# board.net
KiCad netlist of a schematic drawn in EAGLE
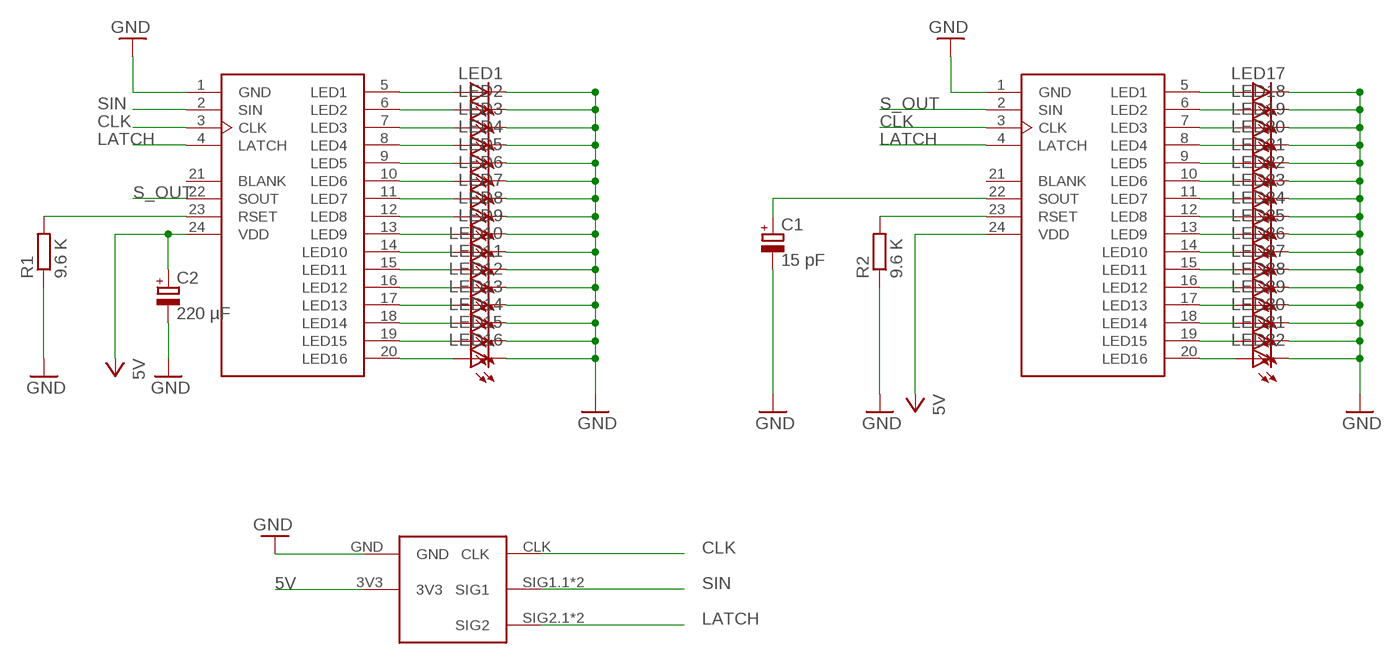
[diagram p0: schematic, sheet 1]

(export (version "E")
  (design (tool "Eeschema 10.0.6"))
  (components
    (comp (ref "C1")
      (value "15 pF")
      (footprint "eagle-import:E5-8,5")
      (libsource (lib "eagle-import") (part "CPOL-EUE5-8.5"))
    )
    (comp (ref "C2")
      (value "220 µF")
      (footprint "eagle-import:E5-8,5")
      (libsource (lib "eagle-import") (part "CPOL-EUE5-8.5"))
    )
    (comp (ref "IC1")
      (value "CAT4016")
      (footprint "eagle-import:SOIC24W")
      (libsource (lib "eagle-import") (part "CAT4016"))
    )
    (comp (ref "IC2")
      (value "CAT4016")
      (footprint "eagle-import:SOIC24W")
      (libsource (lib "eagle-import") (part "CAT4016"))
    )
    (comp (ref "LED1")
      (value "LEDCHIPLED-0603-TTW")
      (footprint "eagle-import:CHIPLED-0603-TTW")
      (libsource (lib "eagle-import") (part "LEDCHIPLED-0603-TTW"))
    )
    (comp (ref "LED2")
      (value "LEDCHIPLED-0603-TTW")
      (footprint "eagle-import:CHIPLED-0603-TTW")
      (libsource (lib "eagle-import") (part "LEDCHIPLED-0603-TTW"))
    )
    (comp (ref "LED3")
      (value "LEDCHIPLED-0603-TTW")
      (footprint "eagle-import:CHIPLED-0603-TTW")
      (libsource (lib "eagle-import") (part "LEDCHIPLED-0603-TTW"))
    )
    (comp (ref "LED4")
      (value "LEDCHIPLED-0603-TTW")
      (footprint "eagle-import:CHIPLED-0603-TTW")
      (libsource (lib "eagle-import") (part "LEDCHIPLED-0603-TTW"))
    )
    (comp (ref "LED5")
      (value "LEDCHIPLED-0603-TTW")
      (footprint "eagle-import:CHIPLED-0603-TTW")
      (libsource (lib "eagle-import") (part "LEDCHIPLED-0603-TTW"))
    )
    (comp (ref "LED6")
      (value "LEDCHIPLED-0603-TTW")
      (footprint "eagle-import:CHIPLED-0603-TTW")
      (libsource (lib "eagle-import") (part "LEDCHIPLED-0603-TTW"))
    )
    (comp (ref "LED7")
      (value "LEDCHIPLED-0603-TTW")
      (footprint "eagle-import:CHIPLED-0603-TTW")
      (libsource (lib "eagle-import") (part "LEDCHIPLED-0603-TTW"))
    )
    (comp (ref "LED8")
      (value "LEDCHIPLED-0603-TTW")
      (footprint "eagle-import:CHIPLED-0603-TTW")
      (libsource (lib "eagle-import") (part "LEDCHIPLED-0603-TTW"))
    )
    (comp (ref "LED9")
      (value "LEDCHIPLED-0603-TTW")
      (footprint "eagle-import:CHIPLED-0603-TTW")
      (libsource (lib "eagle-import") (part "LEDCHIPLED-0603-TTW"))
    )
    (comp (ref "LED10")
      (value "LEDCHIPLED-0603-TTW")
      (footprint "eagle-import:CHIPLED-0603-TTW")
      (libsource (lib "eagle-import") (part "LEDCHIPLED-0603-TTW"))
    )
    (comp (ref "LED11")
      (value "LEDCHIPLED-0603-TTW")
      (footprint "eagle-import:CHIPLED-0603-TTW")
      (libsource (lib "eagle-import") (part "LEDCHIPLED-0603-TTW"))
    )
    (comp (ref "LED12")
      (value "LEDCHIPLED-0603-TTW")
      (footprint "eagle-import:CHIPLED-0603-TTW")
      (libsource (lib "eagle-import") (part "LEDCHIPLED-0603-TTW"))
    )
    (comp (ref "LED13")
      (value "LEDCHIPLED-0603-TTW")
      (footprint "eagle-import:CHIPLED-0603-TTW")
      (libsource (lib "eagle-import") (part "LEDCHIPLED-0603-TTW"))
    )
    (comp (ref "LED14")
      (value "LEDCHIPLED-0603-TTW")
      (footprint "eagle-import:CHIPLED-0603-TTW")
      (libsource (lib "eagle-import") (part "LEDCHIPLED-0603-TTW"))
    )
    (comp (ref "LED15")
      (value "LEDCHIPLED-0603-TTW")
      (footprint "eagle-import:CHIPLED-0603-TTW")
      (libsource (lib "eagle-import") (part "LEDCHIPLED-0603-TTW"))
    )
    (comp (ref "LED16")
      (value "LEDCHIPLED-0603-TTW")
      (footprint "eagle-import:CHIPLED-0603-TTW")
      (libsource (lib "eagle-import") (part "LEDCHIPLED-0603-TTW"))
    )
    (comp (ref "LED17")
      (value "LEDCHIPLED-0603-TTW")
      (footprint "eagle-import:CHIPLED-0603-TTW")
      (libsource (lib "eagle-import") (part "LEDCHIPLED-0603-TTW"))
    )
    (comp (ref "LED18")
      (value "LEDCHIPLED-0603-TTW")
      (footprint "eagle-import:CHIPLED-0603-TTW")
      (libsource (lib "eagle-import") (part "LEDCHIPLED-0603-TTW"))
    )
    (comp (ref "LED19")
      (value "LEDCHIPLED-0603-TTW")
      (footprint "eagle-import:CHIPLED-0603-TTW")
      (libsource (lib "eagle-import") (part "LEDCHIPLED-0603-TTW"))
    )
    (comp (ref "LED20")
      (value "LEDCHIPLED-0603-TTW")
      (footprint "eagle-import:CHIPLED-0603-TTW")
      (libsource (lib "eagle-import") (part "LEDCHIPLED-0603-TTW"))
    )
    (comp (ref "LED21")
      (value "LEDCHIPLED-0603-TTW")
      (footprint "eagle-import:CHIPLED-0603-TTW")
      (libsource (lib "eagle-import") (part "LEDCHIPLED-0603-TTW"))
    )
    (comp (ref "LED22")
      (value "LEDCHIPLED-0603-TTW")
      (footprint "eagle-import:CHIPLED-0603-TTW")
      (libsource (lib "eagle-import") (part "LEDCHIPLED-0603-TTW"))
    )
    (comp (ref "LED23")
      (value "LEDCHIPLED-0603-TTW")
      (footprint "eagle-import:CHIPLED-0603-TTW")
      (libsource (lib "eagle-import") (part "LEDCHIPLED-0603-TTW"))
    )
    (comp (ref "LED24")
      (value "LEDCHIPLED-0603-TTW")
      (footprint "eagle-import:CHIPLED-0603-TTW")
      (libsource (lib "eagle-import") (part "LEDCHIPLED-0603-TTW"))
    )
    (comp (ref "LED25")
      (value "LEDCHIPLED-0603-TTW")
      (footprint "eagle-import:CHIPLED-0603-TTW")
      (libsource (lib "eagle-import") (part "LEDCHIPLED-0603-TTW"))
    )
    (comp (ref "LED26")
      (value "LEDCHIPLED-0603-TTW")
      (footprint "eagle-import:CHIPLED-0603-TTW")
      (libsource (lib "eagle-import") (part "LEDCHIPLED-0603-TTW"))
    )
    (comp (ref "LED27")
      (value "LEDCHIPLED-0603-TTW")
      (footprint "eagle-import:CHIPLED-0603-TTW")
      (libsource (lib "eagle-import") (part "LEDCHIPLED-0603-TTW"))
    )
    (comp (ref "LED28")
      (value "LEDCHIPLED-0603-TTW")
      (footprint "eagle-import:CHIPLED-0603-TTW")
      (libsource (lib "eagle-import") (part "LEDCHIPLED-0603-TTW"))
    )
    (comp (ref "LED29")
      (value "LEDCHIPLED-0603-TTW")
      (footprint "eagle-import:CHIPLED-0603-TTW")
      (libsource (lib "eagle-import") (part "LEDCHIPLED-0603-TTW"))
    )
    (comp (ref "LED30")
      (value "LEDCHIPLED-0603-TTW")
      (footprint "eagle-import:CHIPLED-0603-TTW")
      (libsource (lib "eagle-import") (part "LEDCHIPLED-0603-TTW"))
    )
    (comp (ref "LED31")
      (value "LEDCHIPLED-0603-TTW")
      (footprint "eagle-import:CHIPLED-0603-TTW")
      (libsource (lib "eagle-import") (part "LEDCHIPLED-0603-TTW"))
    )
    (comp (ref "LED32")
      (value "LEDCHIPLED-0603-TTW")
      (footprint "eagle-import:CHIPLED-0603-TTW")
      (libsource (lib "eagle-import") (part "LEDCHIPLED-0603-TTW"))
    )
    (comp (ref "R1")
      (value "9.6 K")
      (footprint "eagle-import:0207_10")
      (libsource (lib "eagle-import") (part "R-EU_0207/10"))
    )
    (comp (ref "R2")
      (value "9.6 K")
      (footprint "eagle-import:0207_10")
      (libsource (lib "eagle-import") (part "R-EU_0207/10"))
    )
    (comp (ref "U$1")
      (value "SLIP-RING-INVERSE")
      (footprint "eagle-import:SLIP-RING-INVERSE")
      (libsource (lib "eagle-import") (part "SLIP-RING-INVERSE"))
    )
  )
  (nets
    (net (code "1") (name "/CLK") (class "Default")
      (node (ref "IC1") (pin "3") (pinfunction "CLK_3") (pintype "bidirectional"))
      (node (ref "IC2") (pin "3") (pinfunction "CLK_3") (pintype "bidirectional"))
      (node (ref "U$1") (pin "CLK") (pinfunction "CLK_CLK") (pintype "bidirectional"))
    )
    (net (code "2") (name "/LATCH") (class "Default")
      (node (ref "IC1") (pin "4") (pinfunction "LATCH_4") (pintype "bidirectional"))
      (node (ref "IC2") (pin "4") (pinfunction "LATCH_4") (pintype "bidirectional"))
      (node (ref "U$1") (pin "SIG2.1") (pinfunction "SIG2_SIG2.1") (pintype "bidirectional"))
      (node (ref "U$1") (pin "SIG2.2") (pinfunction "SIG2_SIG2.2") (pintype "bidirectional"))
    )
    (net (code "3") (name "/SIN") (class "Default")
      (node (ref "IC1") (pin "2") (pinfunction "SIN_2") (pintype "bidirectional"))
      (node (ref "U$1") (pin "SIG1.1") (pinfunction "SIG1_SIG1.1") (pintype "bidirectional"))
      (node (ref "U$1") (pin "SIG1.2") (pinfunction "SIG1_SIG1.2") (pintype "bidirectional"))
    )
    (net (code "4") (name "/S_OUT") (class "Default")
      (node (ref "IC1") (pin "22") (pinfunction "SOUT_22") (pintype "bidirectional"))
      (node (ref "IC2") (pin "2") (pinfunction "SIN_2") (pintype "bidirectional"))
    )
    (net (code "5") (name "5V") (class "Default")
      (node (ref "C2") (pin "+") (pinfunction "+_+") (pintype "passive"))
      (node (ref "IC1") (pin "24") (pinfunction "VDD_24") (pintype "bidirectional"))
      (node (ref "IC2") (pin "24") (pinfunction "VDD_24") (pintype "bidirectional"))
      (node (ref "U$1") (pin "3V3") (pinfunction "3V3_3V3") (pintype "bidirectional"))
    )
    (net (code "6") (name "GND") (class "Default")
      (node (ref "C1") (pin "-") (pinfunction "-_-") (pintype "passive"))
      (node (ref "C2") (pin "-") (pinfunction "-_-") (pintype "passive"))
      (node (ref "IC1") (pin "1") (pinfunction "GND_1") (pintype "bidirectional"))
      (node (ref "IC2") (pin "1") (pinfunction "GND_1") (pintype "bidirectional"))
      (node (ref "LED1") (pin "C@1") (pinfunction "C_C@1") (pintype "passive"))
      (node (ref "LED10") (pin "C@1") (pinfunction "C_C@1") (pintype "passive"))
      (node (ref "LED11") (pin "C@1") (pinfunction "C_C@1") (pintype "passive"))
      (node (ref "LED12") (pin "C@1") (pinfunction "C_C@1") (pintype "passive"))
      (node (ref "LED13") (pin "C@1") (pinfunction "C_C@1") (pintype "passive"))
      (node (ref "LED14") (pin "C@1") (pinfunction "C_C@1") (pintype "passive"))
      (node (ref "LED15") (pin "C@1") (pinfunction "C_C@1") (pintype "passive"))
      (node (ref "LED16") (pin "C@1") (pinfunction "C_C@1") (pintype "passive"))
      (node (ref "LED17") (pin "C@1") (pinfunction "C_C@1") (pintype "passive"))
      (node (ref "LED18") (pin "C@1") (pinfunction "C_C@1") (pintype "passive"))
      (node (ref "LED19") (pin "C@1") (pinfunction "C_C@1") (pintype "passive"))
      (node (ref "LED2") (pin "C@1") (pinfunction "C_C@1") (pintype "passive"))
      (node (ref "LED20") (pin "C@1") (pinfunction "C_C@1") (pintype "passive"))
      (node (ref "LED21") (pin "C@1") (pinfunction "C_C@1") (pintype "passive"))
      (node (ref "LED22") (pin "C@1") (pinfunction "C_C@1") (pintype "passive"))
      (node (ref "LED23") (pin "C@1") (pinfunction "C_C@1") (pintype "passive"))
      (node (ref "LED24") (pin "C@1") (pinfunction "C_C@1") (pintype "passive"))
      (node (ref "LED25") (pin "C@1") (pinfunction "C_C@1") (pintype "passive"))
      (node (ref "LED26") (pin "C@1") (pinfunction "C_C@1") (pintype "passive"))
      (node (ref "LED27") (pin "C@1") (pinfunction "C_C@1") (pintype "passive"))
      (node (ref "LED28") (pin "C@1") (pinfunction "C_C@1") (pintype "passive"))
      (node (ref "LED29") (pin "C@1") (pinfunction "C_C@1") (pintype "passive"))
      (node (ref "LED3") (pin "C@1") (pinfunction "C_C@1") (pintype "passive"))
      (node (ref "LED30") (pin "C@1") (pinfunction "C_C@1") (pintype "passive"))
      (node (ref "LED31") (pin "C@1") (pinfunction "C_C@1") (pintype "passive"))
      (node (ref "LED32") (pin "C@1") (pinfunction "C_C@1") (pintype "passive"))
      (node (ref "LED4") (pin "C@1") (pinfunction "C_C@1") (pintype "passive"))
      (node (ref "LED5") (pin "C@1") (pinfunction "C_C@1") (pintype "passive"))
      (node (ref "LED6") (pin "C@1") (pinfunction "C_C@1") (pintype "passive"))
      (node (ref "LED7") (pin "C@1") (pinfunction "C_C@1") (pintype "passive"))
      (node (ref "LED8") (pin "C@1") (pinfunction "C_C@1") (pintype "passive"))
      (node (ref "LED9") (pin "C@1") (pinfunction "C_C@1") (pintype "passive"))
      (node (ref "R1") (pin "1") (pinfunction "1_1") (pintype "passive"))
      (node (ref "R2") (pin "1") (pinfunction "1_1") (pintype "passive"))
      (node (ref "U$1") (pin "GND") (pinfunction "GND_GND") (pintype "bidirectional"))
    )
    (net (code "7") (name "Net-(IC1-LED1)") (class "Default")
      (node (ref "IC1") (pin "5") (pinfunction "LED1_5") (pintype "bidirectional"))
      (node (ref "LED1") (pin "A@1") (pinfunction "A_A@1") (pintype "passive"))
    )
    (net (code "8") (name "Net-(IC1-LED2)") (class "Default")
      (node (ref "IC1") (pin "6") (pinfunction "LED2_6") (pintype "bidirectional"))
      (node (ref "LED2") (pin "A@1") (pinfunction "A_A@1") (pintype "passive"))
    )
    (net (code "9") (name "Net-(IC1-LED3)") (class "Default")
      (node (ref "IC1") (pin "7") (pinfunction "LED3_7") (pintype "bidirectional"))
      (node (ref "LED3") (pin "A@1") (pinfunction "A_A@1") (pintype "passive"))
    )
    (net (code "10") (name "Net-(IC1-LED4)") (class "Default")
      (node (ref "IC1") (pin "8") (pinfunction "LED4_8") (pintype "bidirectional"))
      (node (ref "LED4") (pin "A@1") (pinfunction "A_A@1") (pintype "passive"))
    )
    (net (code "11") (name "Net-(IC1-LED5)") (class "Default")
      (node (ref "IC1") (pin "9") (pinfunction "LED5_9") (pintype "bidirectional"))
      (node (ref "LED5") (pin "A@1") (pinfunction "A_A@1") (pintype "passive"))
    )
    (net (code "12") (name "Net-(IC1-LED6)") (class "Default")
      (node (ref "IC1") (pin "10") (pinfunction "LED6_10") (pintype "bidirectional"))
      (node (ref "LED6") (pin "A@1") (pinfunction "A_A@1") (pintype "passive"))
    )
    (net (code "13") (name "Net-(IC1-LED7)") (class "Default")
      (node (ref "IC1") (pin "11") (pinfunction "LED7_11") (pintype "bidirectional"))
      (node (ref "LED7") (pin "A@1") (pinfunction "A_A@1") (pintype "passive"))
    )
    (net (code "14") (name "Net-(IC1-LED8)") (class "Default")
      (node (ref "IC1") (pin "12") (pinfunction "LED8_12") (pintype "bidirectional"))
      (node (ref "LED8") (pin "A@1") (pinfunction "A_A@1") (pintype "passive"))
    )
    (net (code "15") (name "Net-(IC1-LED9)") (class "Default")
      (node (ref "IC1") (pin "13") (pinfunction "LED9_13") (pintype "bidirectional"))
      (node (ref "LED9") (pin "A@1") (pinfunction "A_A@1") (pintype "passive"))
    )
    (net (code "16") (name "Net-(IC1-LED10)") (class "Default")
      (node (ref "IC1") (pin "14") (pinfunction "LED10_14") (pintype "bidirectional"))
      (node (ref "LED10") (pin "A@1") (pinfunction "A_A@1") (pintype "passive"))
    )
    (net (code "17") (name "Net-(IC1-LED11)") (class "Default")
      (node (ref "IC1") (pin "15") (pinfunction "LED11_15") (pintype "bidirectional"))
      (node (ref "LED11") (pin "A@1") (pinfunction "A_A@1") (pintype "passive"))
    )
    (net (code "18") (name "Net-(IC1-LED12)") (class "Default")
      (node (ref "IC1") (pin "16") (pinfunction "LED12_16") (pintype "bidirectional"))
      (node (ref "LED12") (pin "A@1") (pinfunction "A_A@1") (pintype "passive"))
    )
    (net (code "19") (name "Net-(IC1-LED13)") (class "Default")
      (node (ref "IC1") (pin "17") (pinfunction "LED13_17") (pintype "bidirectional"))
      (node (ref "LED13") (pin "A@1") (pinfunction "A_A@1") (pintype "passive"))
    )
    (net (code "20") (name "Net-(IC1-LED14)") (class "Default")
      (node (ref "IC1") (pin "18") (pinfunction "LED14_18") (pintype "bidirectional"))
      (node (ref "LED14") (pin "A@1") (pinfunction "A_A@1") (pintype "passive"))
    )
    (net (code "21") (name "Net-(IC1-LED15)") (class "Default")
      (node (ref "IC1") (pin "19") (pinfunction "LED15_19") (pintype "bidirectional"))
      (node (ref "LED15") (pin "A@1") (pinfunction "A_A@1") (pintype "passive"))
    )
    (net (code "22") (name "Net-(IC1-LED16)") (class "Default")
      (node (ref "IC1") (pin "20") (pinfunction "LED16_20") (pintype "bidirectional"))
      (node (ref "LED16") (pin "A@1") (pinfunction "A_A@1") (pintype "passive"))
    )
    (net (code "23") (name "Net-(IC1-RSET)") (class "Default")
      (node (ref "IC1") (pin "23") (pinfunction "RSET_23") (pintype "bidirectional"))
      (node (ref "R1") (pin "2") (pinfunction "2_2") (pintype "passive"))
    )
    (net (code "24") (name "Net-(IC2-LED1)") (class "Default")
      (node (ref "IC2") (pin "5") (pinfunction "LED1_5") (pintype "bidirectional"))
      (node (ref "LED17") (pin "A@1") (pinfunction "A_A@1") (pintype "passive"))
    )
    (net (code "25") (name "Net-(IC2-LED2)") (class "Default")
      (node (ref "IC2") (pin "6") (pinfunction "LED2_6") (pintype "bidirectional"))
      (node (ref "LED18") (pin "A@1") (pinfunction "A_A@1") (pintype "passive"))
    )
    (net (code "26") (name "Net-(IC2-LED3)") (class "Default")
      (node (ref "IC2") (pin "7") (pinfunction "LED3_7") (pintype "bidirectional"))
      (node (ref "LED19") (pin "A@1") (pinfunction "A_A@1") (pintype "passive"))
    )
    (net (code "27") (name "Net-(IC2-LED4)") (class "Default")
      (node (ref "IC2") (pin "8") (pinfunction "LED4_8") (pintype "bidirectional"))
      (node (ref "LED20") (pin "A@1") (pinfunction "A_A@1") (pintype "passive"))
    )
    (net (code "28") (name "Net-(IC2-LED5)") (class "Default")
      (node (ref "IC2") (pin "9") (pinfunction "LED5_9") (pintype "bidirectional"))
      (node (ref "LED21") (pin "A@1") (pinfunction "A_A@1") (pintype "passive"))
    )
    (net (code "29") (name "Net-(IC2-LED6)") (class "Default")
      (node (ref "IC2") (pin "10") (pinfunction "LED6_10") (pintype "bidirectional"))
      (node (ref "LED22") (pin "A@1") (pinfunction "A_A@1") (pintype "passive"))
    )
    (net (code "30") (name "Net-(IC2-LED7)") (class "Default")
      (node (ref "IC2") (pin "11") (pinfunction "LED7_11") (pintype "bidirectional"))
      (node (ref "LED23") (pin "A@1") (pinfunction "A_A@1") (pintype "passive"))
    )
    (net (code "31") (name "Net-(IC2-LED8)") (class "Default")
      (node (ref "IC2") (pin "12") (pinfunction "LED8_12") (pintype "bidirectional"))
      (node (ref "LED24") (pin "A@1") (pinfunction "A_A@1") (pintype "passive"))
    )
    (net (code "32") (name "Net-(IC2-LED9)") (class "Default")
      (node (ref "IC2") (pin "13") (pinfunction "LED9_13") (pintype "bidirectional"))
      (node (ref "LED25") (pin "A@1") (pinfunction "A_A@1") (pintype "passive"))
    )
    (net (code "33") (name "Net-(IC2-LED10)") (class "Default")
      (node (ref "IC2") (pin "14") (pinfunction "LED10_14") (pintype "bidirectional"))
      (node (ref "LED26") (pin "A@1") (pinfunction "A_A@1") (pintype "passive"))
    )
    (net (code "34") (name "Net-(IC2-LED11)") (class "Default")
      (node (ref "IC2") (pin "15") (pinfunction "LED11_15") (pintype "bidirectional"))
      (node (ref "LED27") (pin "A@1") (pinfunction "A_A@1") (pintype "passive"))
    )
    (net (code "35") (name "Net-(IC2-LED12)") (class "Default")
      (node (ref "IC2") (pin "16") (pinfunction "LED12_16") (pintype "bidirectional"))
      (node (ref "LED28") (pin "A@1") (pinfunction "A_A@1") (pintype "passive"))
    )
    (net (code "36") (name "Net-(IC2-LED13)") (class "Default")
      (node (ref "IC2") (pin "17") (pinfunction "LED13_17") (pintype "bidirectional"))
      (node (ref "LED29") (pin "A@1") (pinfunction "A_A@1") (pintype "passive"))
    )
    (net (code "37") (name "Net-(IC2-LED14)") (class "Default")
      (node (ref "IC2") (pin "18") (pinfunction "LED14_18") (pintype "bidirectional"))
      (node (ref "LED30") (pin "A@1") (pinfunction "A_A@1") (pintype "passive"))
    )
    (net (code "38") (name "Net-(IC2-LED15)") (class "Default")
      (node (ref "IC2") (pin "19") (pinfunction "LED15_19") (pintype "bidirectional"))
      (node (ref "LED31") (pin "A@1") (pinfunction "A_A@1") (pintype "passive"))
    )
    (net (code "39") (name "Net-(IC2-LED16)") (class "Default")
      (node (ref "IC2") (pin "20") (pinfunction "LED16_20") (pintype "bidirectional"))
      (node (ref "LED32") (pin "A@1") (pinfunction "A_A@1") (pintype "passive"))
    )
    (net (code "40") (name "Net-(IC2-RSET)") (class "Default")
      (node (ref "IC2") (pin "23") (pinfunction "RSET_23") (pintype "bidirectional"))
      (node (ref "R2") (pin "2") (pinfunction "2_2") (pintype "passive"))
    )
    (net (code "41") (name "Net-(IC2-SOUT)") (class "Default")
      (node (ref "C1") (pin "+") (pinfunction "+_+") (pintype "passive"))
      (node (ref "IC2") (pin "22") (pinfunction "SOUT_22") (pintype "bidirectional"))
    )
    (net (code "42") (name "unconnected-(IC1-BLANK-Pad21)") (class "Default")
      (node (ref "IC1") (pin "21") (pinfunction "BLANK_21") (pintype "bidirectional"))
    )
    (net (code "43") (name "unconnected-(IC2-BLANK-Pad21)") (class "Default")
      (node (ref "IC2") (pin "21") (pinfunction "BLANK_21") (pintype "bidirectional"))
    )
  )
)
